# Solar_Harvester.net
KiCad netlist of a schematic drawn in EAGLE
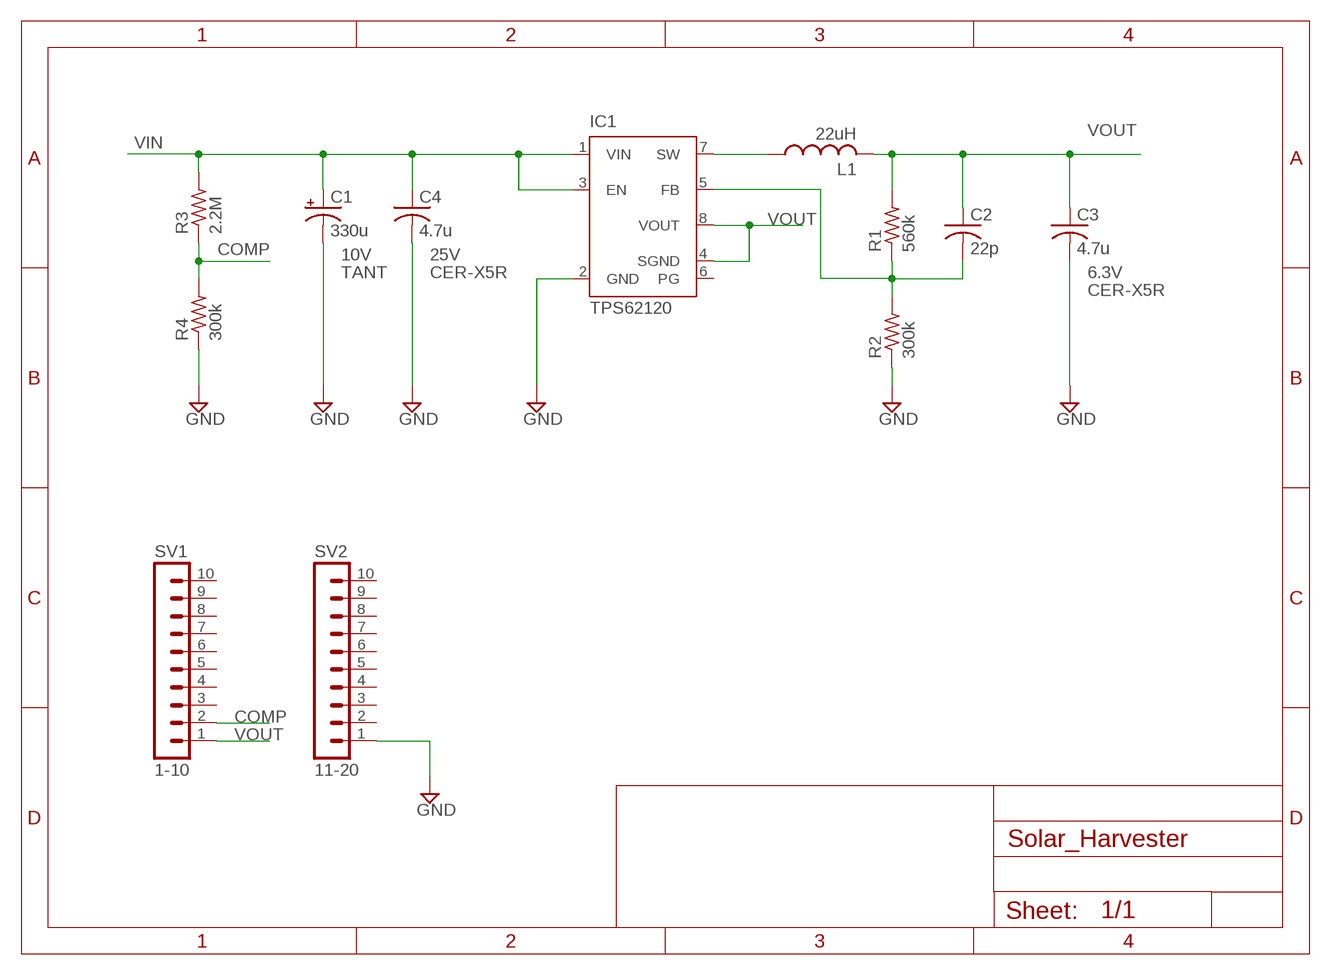
[diagram p0: schematic, sheet 1]

(export (version "E")
  (design (tool "Eeschema 10.0.6"))
  (components
    (comp (ref "C1")
      (value "330u")
      (footprint "eagle-import:CT7343")
      (fields (field (name "TYPE") "TANT") (field (name "VOLTAGE") "10V"))
      (libsource (lib "eagle-import") (part "CPOL-USCT7343"))
    )
    (comp (ref "C2")
      (value "22p")
      (footprint "eagle-import:C0603K")
      (libsource (lib "eagle-import") (part "C-USC0603K"))
    )
    (comp (ref "C3")
      (value "4.7u")
      (footprint "eagle-import:C0603K")
      (fields (field (name "TYPE") "CER-X5R") (field (name "VOLTAGE") "6.3V"))
      (libsource (lib "eagle-import") (part "C-USC0603K"))
    )
    (comp (ref "C4")
      (value "4.7u")
      (footprint "eagle-import:C0805K")
      (fields (field (name "TYPE") "CER-X5R") (field (name "VOLTAGE") "25V"))
      (libsource (lib "eagle-import") (part "C-USC0805K"))
    )
    (comp (ref "IC1")
      (value "TPS62120")
      (footprint "eagle-import:DCN-R-PDSO-G8")
      (libsource (lib "eagle-import") (part "TPS62120"))
    )
    (comp (ref "L1")
      (value "22uH")
      (footprint "eagle-import:L2825P")
      (libsource (lib "eagle-import") (part "L-USL2825P"))
    )
    (comp (ref "R1")
      (value "560k")
      (footprint "eagle-import:R0603")
      (libsource (lib "eagle-import") (part "R-US_R0603"))
    )
    (comp (ref "R2")
      (value "300k")
      (footprint "eagle-import:R0603")
      (libsource (lib "eagle-import") (part "R-US_R0603"))
    )
    (comp (ref "R3")
      (value "2.2M")
      (footprint "eagle-import:R0603")
      (libsource (lib "eagle-import") (part "R-US_R0603"))
    )
    (comp (ref "R4")
      (value "300k")
      (footprint "eagle-import:R0603")
      (libsource (lib "eagle-import") (part "R-US_R0603"))
    )
    (comp (ref "SV1")
      (value "1-10")
      (footprint "eagle-import:MA10-1")
      (libsource (lib "eagle-import") (part "MA10-1"))
    )
    (comp (ref "SV2")
      (value "11-20")
      (footprint "eagle-import:MA10-1")
      (libsource (lib "eagle-import") (part "MA10-1"))
    )
  )
  (nets
    (net (code "1") (name "/COMP") (class "Default")
      (node (ref "R3") (pin "1") (pinfunction "1_1") (pintype "passive"))
      (node (ref "R4") (pin "2") (pinfunction "2_2") (pintype "passive"))
      (node (ref "SV1") (pin "2") (pinfunction "2_2") (pintype "passive"))
    )
    (net (code "2") (name "/VIN") (class "Default")
      (node (ref "C1") (pin "+") (pinfunction "+_+") (pintype "passive"))
      (node (ref "C4") (pin "1") (pinfunction "1_1") (pintype "passive"))
      (node (ref "IC1") (pin "1") (pinfunction "VIN_1") (pintype "input"))
      (node (ref "IC1") (pin "3") (pinfunction "EN_3") (pintype "input"))
      (node (ref "R3") (pin "2") (pinfunction "2_2") (pintype "passive"))
    )
    (net (code "3") (name "/VOUT") (class "Default")
      (node (ref "C2") (pin "1") (pinfunction "1_1") (pintype "passive"))
      (node (ref "C3") (pin "1") (pinfunction "1_1") (pintype "passive"))
      (node (ref "IC1") (pin "4") (pinfunction "SGND_4") (pintype "passive"))
      (node (ref "IC1") (pin "8") (pinfunction "VOUT_8") (pintype "output"))
      (node (ref "L1") (pin "2") (pinfunction "2_2") (pintype "passive"))
      (node (ref "R1") (pin "2") (pinfunction "2_2") (pintype "passive"))
      (node (ref "SV1") (pin "1") (pinfunction "1_1") (pintype "passive"))
    )
    (net (code "4") (name "GND") (class "Default")
      (node (ref "C1") (pin "-") (pinfunction "-_-") (pintype "passive"))
      (node (ref "C3") (pin "2") (pinfunction "2_2") (pintype "passive"))
      (node (ref "C4") (pin "2") (pinfunction "2_2") (pintype "passive"))
      (node (ref "IC1") (pin "2") (pinfunction "GND_2") (pintype "power_in"))
      (node (ref "R2") (pin "1") (pinfunction "1_1") (pintype "passive"))
      (node (ref "R4") (pin "1") (pinfunction "1_1") (pintype "passive"))
      (node (ref "SV2") (pin "1") (pinfunction "1_1") (pintype "passive"))
    )
    (net (code "5") (name "Net-(IC1-FB)") (class "Default")
      (node (ref "C2") (pin "2") (pinfunction "2_2") (pintype "passive"))
      (node (ref "IC1") (pin "5") (pinfunction "FB_5") (pintype "input"))
      (node (ref "R1") (pin "1") (pinfunction "1_1") (pintype "passive"))
      (node (ref "R2") (pin "2") (pinfunction "2_2") (pintype "passive"))
    )
    (net (code "6") (name "Net-(IC1-SW)") (class "Default")
      (node (ref "IC1") (pin "7") (pinfunction "SW_7") (pintype "output"))
      (node (ref "L1") (pin "1") (pinfunction "1_1") (pintype "passive"))
    )
    (net (code "7") (name "unconnected-(IC1-PG-Pad6)") (class "Default")
      (node (ref "IC1") (pin "6") (pinfunction "PG_6") (pintype "passive"))
    )
    (net (code "8") (name "unconnected-(SV1-Pad3)") (class "Default")
      (node (ref "SV1") (pin "3") (pinfunction "3_3") (pintype "passive"))
    )
    (net (code "9") (name "unconnected-(SV1-Pad4)") (class "Default")
      (node (ref "SV1") (pin "4") (pinfunction "4_4") (pintype "passive"))
    )
    (net (code "10") (name "unconnected-(SV1-Pad5)") (class "Default")
      (node (ref "SV1") (pin "5") (pinfunction "5_5") (pintype "passive"))
    )
    (net (code "11") (name "unconnected-(SV1-Pad6)") (class "Default")
      (node (ref "SV1") (pin "6") (pinfunction "6_6") (pintype "passive"))
    )
    (net (code "12") (name "unconnected-(SV1-Pad7)") (class "Default")
      (node (ref "SV1") (pin "7") (pinfunction "7_7") (pintype "passive"))
    )
    (net (code "13") (name "unconnected-(SV1-Pad8)") (class "Default")
      (node (ref "SV1") (pin "8") (pinfunction "8_8") (pintype "passive"))
    )
    (net (code "14") (name "unconnected-(SV1-Pad9)") (class "Default")
      (node (ref "SV1") (pin "9") (pinfunction "9_9") (pintype "passive"))
    )
    (net (code "15") (name "unconnected-(SV1-Pad10)") (class "Default")
      (node (ref "SV1") (pin "10") (pinfunction "10_10") (pintype "passive"))
    )
    (net (code "16") (name "unconnected-(SV2-Pad2)") (class "Default")
      (node (ref "SV2") (pin "2") (pinfunction "2_2") (pintype "passive"))
    )
    (net (code "17") (name "unconnected-(SV2-Pad3)") (class "Default")
      (node (ref "SV2") (pin "3") (pinfunction "3_3") (pintype "passive"))
    )
    (net (code "18") (name "unconnected-(SV2-Pad4)") (class "Default")
      (node (ref "SV2") (pin "4") (pinfunction "4_4") (pintype "passive"))
    )
    (net (code "19") (name "unconnected-(SV2-Pad5)") (class "Default")
      (node (ref "SV2") (pin "5") (pinfunction "5_5") (pintype "passive"))
    )
    (net (code "20") (name "unconnected-(SV2-Pad6)") (class "Default")
      (node (ref "SV2") (pin "6") (pinfunction "6_6") (pintype "passive"))
    )
    (net (code "21") (name "unconnected-(SV2-Pad7)") (class "Default")
      (node (ref "SV2") (pin "7") (pinfunction "7_7") (pintype "passive"))
    )
    (net (code "22") (name "unconnected-(SV2-Pad8)") (class "Default")
      (node (ref "SV2") (pin "8") (pinfunction "8_8") (pintype "passive"))
    )
    (net (code "23") (name "unconnected-(SV2-Pad9)") (class "Default")
      (node (ref "SV2") (pin "9") (pinfunction "9_9") (pintype "passive"))
    )
    (net (code "24") (name "unconnected-(SV2-Pad10)") (class "Default")
      (node (ref "SV2") (pin "10") (pinfunction "10_10") (pintype "passive"))
    )
  )
)
